# Arduino_Pro_Mini_Mother_Board_1_1.net
KiCad netlist of a schematic drawn in EAGLE
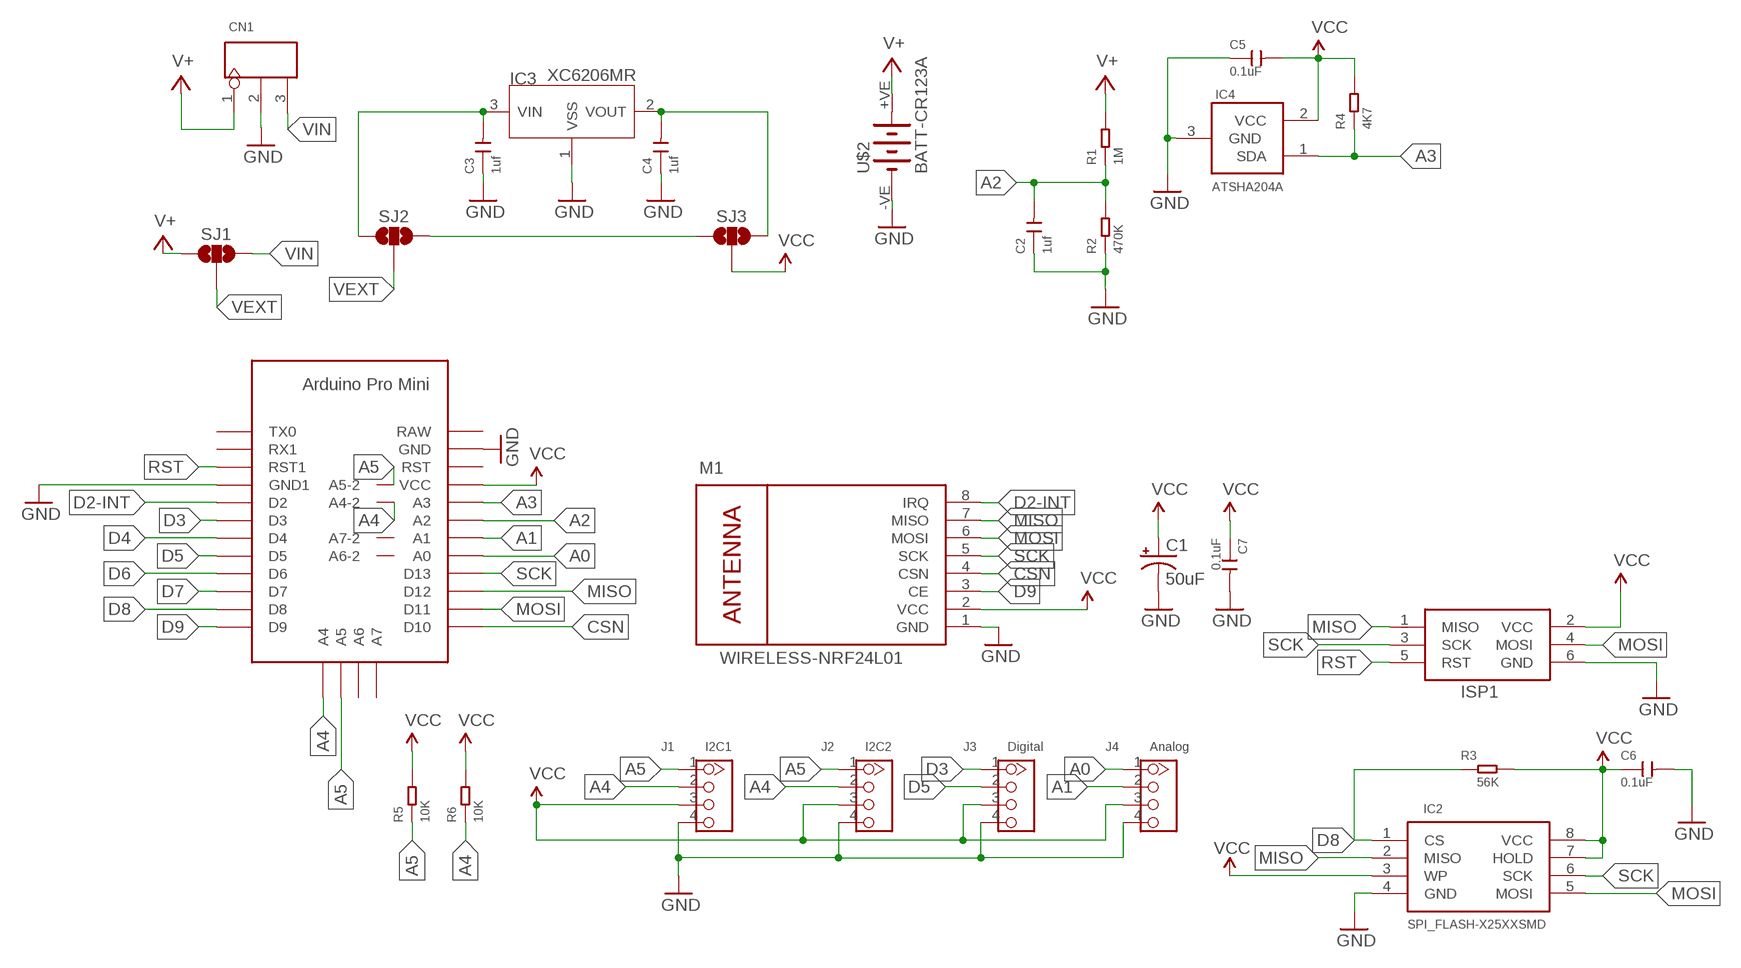
[diagram p0: schematic, sheet 1]

(export (version "E")
  (design (tool "Eeschema 10.0.6"))
  (components
    (comp (ref "ARDUINOPROMINI")
      (value "PRO-MINI-UNIVERSAL")
      (footprint "eagle-import:PRO-MINI-UINIVERSAL")
      (libsource (lib "eagle-import") (part "PRO-MINI-UNIVERSAL"))
    )
    (comp (ref "C1")
      (value "50uF")
      (footprint "eagle-import:EIA6032")
      (libsource (lib "eagle-import") (part "CAP_POL6032"))
    )
    (comp (ref "C2")
      (value "1uf")
      (footprint "eagle-import:C0603")
      (fields (field (name "MPN") "CC0603KRX7R8BB105"))
      (libsource (lib "eagle-import") (part "CERAMIC-1UF-25V-10%-X7R(0603)"))
    )
    (comp (ref "C3")
      (value "1uf")
      (footprint "eagle-import:C0603")
      (fields (field (name "MPN") "CC0603KRX7R8BB105"))
      (libsource (lib "eagle-import") (part "CERAMIC-1UF-25V-10%-X7R(0603)"))
    )
    (comp (ref "C4")
      (value "1uf")
      (footprint "eagle-import:C0603")
      (fields (field (name "MPN") "CC0603KRX7R8BB105"))
      (libsource (lib "eagle-import") (part "CERAMIC-1UF-25V-10%-X7R(0603)"))
    )
    (comp (ref "C5")
      (value "0.1uF")
      (footprint "eagle-import:C0603")
      (fields (field (name "MPN") "CC0603KRX7R8BB105"))
      (libsource (lib "eagle-import") (part "CERAMIC-1UF-25V-10%-X7R(0603)"))
    )
    (comp (ref "C6")
      (value "0.1uF")
      (footprint "eagle-import:C0603")
      (fields (field (name "MPN") "CC0603KRX7R8BB105"))
      (libsource (lib "eagle-import") (part "CERAMIC-1UF-25V-10%-X7R(0603)"))
    )
    (comp (ref "C7")
      (value "0.1uF")
      (footprint "eagle-import:C0603")
      (fields (field (name "MPN") "CC0603KRX7R8BB105"))
      (libsource (lib "eagle-import") (part "CERAMIC-1UF-25V-10%-X7R(0603)"))
    )
    (comp (ref "CN1")
      (value "DIP-BLACK-MALE-HEADER-VERT(3P-2.54)")
      (footprint "eagle-import:H3-2.54")
      (libsource (lib "eagle-import") (part "DIP-BLACK-MALE-HEADER-VERT(3P-2.54)"))
    )
    (comp (ref "IC2")
      (value "SPI_FLASH-X25XXSMD")
      (footprint "eagle-import:SO08")
      (libsource (lib "eagle-import") (part "SPI_FLASH-X25XXSMD"))
    )
    (comp (ref "IC3")
      (value "XC6206MR")
      (footprint "eagle-import:SOT23")
      (libsource (lib "eagle-import") (part "XC6206MR"))
    )
    (comp (ref "IC4")
      (value "ATSHA204A")
      (footprint "eagle-import:SOT23")
      (libsource (lib "eagle-import") (part "ATSHA204A"))
    )
    (comp (ref "ISP1")
      (value "AVRISP-6")
      (footprint "eagle-import:AVRISP")
      (libsource (lib "eagle-import") (part "AVRISP-6"))
    )
    (comp (ref "J1")
      (value "I2C1")
      (footprint "eagle-import:HW4-2.0")
      (libsource (lib "eagle-import") (part "GROVE-CONNECTOR-DIP(4P-2.0)"))
    )
    (comp (ref "J2")
      (value "I2C2")
      (footprint "eagle-import:HW4-2.0")
      (libsource (lib "eagle-import") (part "GROVE-CONNECTOR-DIP(4P-2.0)"))
    )
    (comp (ref "J3")
      (value "Digital")
      (footprint "eagle-import:HW4-2.0")
      (libsource (lib "eagle-import") (part "GROVE-CONNECTOR-DIP(4P-2.0)"))
    )
    (comp (ref "J4")
      (value "Analog")
      (footprint "eagle-import:HW4-2.0")
      (libsource (lib "eagle-import") (part "GROVE-CONNECTOR-DIP(4P-2.0)"))
    )
    (comp (ref "M1")
      (value "WIRELESS-NRF24L01")
      (footprint "eagle-import:WIRELESS-NRF24L01")
      (libsource (lib "eagle-import") (part "WIRELESS-NRF24L01"))
    )
    (comp (ref "R1")
      (value "1M")
      (footprint "eagle-import:R0603")
      (fields (field (name "MPN") "RC0603FR-071ML"))
      (libsource (lib "eagle-import") (part "SMD-RES-1M-1%-1/10W(0603)"))
    )
    (comp (ref "R2")
      (value "470K")
      (footprint "eagle-import:R0603")
      (fields (field (name "MPN") "RC0603FR-07470KL"))
      (libsource (lib "eagle-import") (part "SMD-RES-470K-1%-1/10W(0603)"))
    )
    (comp (ref "R3")
      (value "56K")
      (footprint "eagle-import:R0603")
      (fields (field (name "MPN") "RC0603FR-07470KL"))
      (libsource (lib "eagle-import") (part "SMD-RES-470K-1%-1/10W(0603)"))
    )
    (comp (ref "R4")
      (value "4K7")
      (footprint "eagle-import:R0603")
      (fields (field (name "MPN") "RC0603FR-07470KL"))
      (libsource (lib "eagle-import") (part "SMD-RES-470K-1%-1/10W(0603)"))
    )
    (comp (ref "R5")
      (value "10K")
      (footprint "eagle-import:R0603")
      (fields (field (name "MPN") "RC0603FR-071ML"))
      (libsource (lib "eagle-import") (part "SMD-RES-1M-1%-1/10W(0603)"))
    )
    (comp (ref "R6")
      (value "10K")
      (footprint "eagle-import:R0603")
      (fields (field (name "MPN") "RC0603FR-071ML"))
      (libsource (lib "eagle-import") (part "SMD-RES-1M-1%-1/10W(0603)"))
    )
    (comp (ref "SJ1")
      (value "SOLDERJUMPER_2WAYS")
      (footprint "eagle-import:SJ_3")
      (libsource (lib "eagle-import") (part "SOLDERJUMPER_2WAYS"))
    )
    (comp (ref "SJ2")
      (value "SOLDERJUMPER_2WAYS")
      (footprint "eagle-import:SJ_3")
      (libsource (lib "eagle-import") (part "SOLDERJUMPER_2WAYS"))
    )
    (comp (ref "SJ3")
      (value "SOLDERJUMPER_2WAYS")
      (footprint "eagle-import:SJ_3")
      (libsource (lib "eagle-import") (part "SOLDERJUMPER_2WAYS"))
    )
    (comp (ref "U$2")
      (value "BATT-CR123A")
      (footprint "eagle-import:KEYSTONE-2_3A")
      (libsource (lib "eagle-import") (part "BATT-CR123A"))
    )
  )
  (nets
    (net (code "1") (name "A0") (class "Default")
      (node (ref "ARDUINOPROMINI") (pin "A0") (pinfunction "A0_A0") (pintype "bidirectional"))
      (node (ref "J4") (pin "1") (pinfunction "1_1") (pintype "bidirectional"))
    )
    (net (code "2") (name "A1") (class "Default")
      (node (ref "ARDUINOPROMINI") (pin "A1") (pinfunction "A1_A1") (pintype "bidirectional"))
      (node (ref "J4") (pin "2") (pinfunction "2_2") (pintype "bidirectional"))
    )
    (net (code "3") (name "A2") (class "Default")
      (node (ref "ARDUINOPROMINI") (pin "A2") (pinfunction "A2_A2") (pintype "bidirectional"))
      (node (ref "C2") (pin "2") (pinfunction "2_2") (pintype "passive"))
      (node (ref "R1") (pin "1") (pinfunction "1_1") (pintype "passive"))
      (node (ref "R2") (pin "2") (pinfunction "2_2") (pintype "passive"))
    )
    (net (code "4") (name "A3") (class "Default")
      (node (ref "ARDUINOPROMINI") (pin "A3") (pinfunction "A3_A3") (pintype "bidirectional"))
      (node (ref "IC4") (pin "1") (pinfunction "SDA_1") (pintype "bidirectional"))
      (node (ref "R4") (pin "1") (pinfunction "1_1") (pintype "passive"))
    )
    (net (code "5") (name "A4") (class "Default")
      (node (ref "ARDUINOPROMINI") (pin "A4") (pinfunction "A4_A4") (pintype "bidirectional"))
      (node (ref "ARDUINOPROMINI") (pin "A4-2") (pinfunction "A4-2_A4-2") (pintype "bidirectional"))
      (node (ref "J1") (pin "2") (pinfunction "2_2") (pintype "bidirectional"))
      (node (ref "J2") (pin "2") (pinfunction "2_2") (pintype "bidirectional"))
      (node (ref "R6") (pin "1") (pinfunction "1_1") (pintype "passive"))
    )
    (net (code "6") (name "A5") (class "Default")
      (node (ref "ARDUINOPROMINI") (pin "A5") (pinfunction "A5_A5") (pintype "bidirectional"))
      (node (ref "ARDUINOPROMINI") (pin "A5-2") (pinfunction "A5-2_A5-2") (pintype "bidirectional"))
      (node (ref "J1") (pin "1") (pinfunction "1_1") (pintype "bidirectional"))
      (node (ref "J2") (pin "1") (pinfunction "1_1") (pintype "bidirectional"))
      (node (ref "R5") (pin "1") (pinfunction "1_1") (pintype "passive"))
    )
    (net (code "7") (name "CSN") (class "Default")
      (node (ref "ARDUINOPROMINI") (pin "D10") (pinfunction "D10_D10") (pintype "bidirectional"))
      (node (ref "M1") (pin "4") (pinfunction "CSN_4") (pintype "bidirectional"))
    )
    (net (code "8") (name "D2-INT") (class "Default")
      (node (ref "ARDUINOPROMINI") (pin "D2") (pinfunction "D2_D2") (pintype "bidirectional"))
      (node (ref "M1") (pin "8") (pinfunction "IRQ_8") (pintype "bidirectional"))
    )
    (net (code "9") (name "D3") (class "Default")
      (node (ref "ARDUINOPROMINI") (pin "D3") (pinfunction "D3_D3") (pintype "bidirectional"))
      (node (ref "J3") (pin "1") (pinfunction "1_1") (pintype "bidirectional"))
    )
    (net (code "10") (name "D4") (class "Default")
      (node (ref "ARDUINOPROMINI") (pin "D4") (pinfunction "D4_D4") (pintype "bidirectional"))
    )
    (net (code "11") (name "D5") (class "Default")
      (node (ref "ARDUINOPROMINI") (pin "D5") (pinfunction "D5_D5") (pintype "bidirectional"))
      (node (ref "J3") (pin "2") (pinfunction "2_2") (pintype "bidirectional"))
    )
    (net (code "12") (name "D6") (class "Default")
      (node (ref "ARDUINOPROMINI") (pin "D6") (pinfunction "D6_D6") (pintype "bidirectional"))
    )
    (net (code "13") (name "D7") (class "Default")
      (node (ref "ARDUINOPROMINI") (pin "D7") (pinfunction "D7_D7") (pintype "bidirectional"))
    )
    (net (code "14") (name "D8") (class "Default")
      (node (ref "ARDUINOPROMINI") (pin "D8") (pinfunction "D8_D8") (pintype "bidirectional"))
      (node (ref "IC2") (pin "1") (pinfunction "CS_1") (pintype "bidirectional"))
      (node (ref "R3") (pin "1") (pinfunction "1_1") (pintype "passive"))
    )
    (net (code "15") (name "D9") (class "Default")
      (node (ref "ARDUINOPROMINI") (pin "D9") (pinfunction "D9_D9") (pintype "bidirectional"))
      (node (ref "M1") (pin "3") (pinfunction "CE_3") (pintype "bidirectional"))
    )
    (net (code "16") (name "GND") (class "Default")
      (node (ref "ARDUINOPROMINI") (pin "GND0") (pinfunction "GND_GND0") (pintype "bidirectional"))
      (node (ref "ARDUINOPROMINI") (pin "GND1") (pinfunction "GND1_GND1") (pintype "bidirectional"))
      (node (ref "C1") (pin "P$2") (pinfunction "-_P$2") (pintype "passive"))
      (node (ref "C2") (pin "1") (pinfunction "1_1") (pintype "passive"))
      (node (ref "C3") (pin "1") (pinfunction "1_1") (pintype "passive"))
      (node (ref "C4") (pin "1") (pinfunction "1_1") (pintype "passive"))
      (node (ref "C5") (pin "1") (pinfunction "1_1") (pintype "passive"))
      (node (ref "C6") (pin "2") (pinfunction "2_2") (pintype "passive"))
      (node (ref "C7") (pin "2") (pinfunction "2_2") (pintype "passive"))
      (node (ref "CN1") (pin "2") (pinfunction "P$2_2") (pintype "bidirectional"))
      (node (ref "IC2") (pin "4") (pinfunction "GND_4") (pintype "bidirectional"))
      (node (ref "IC3") (pin "1") (pinfunction "VSS_1") (pintype "power_in"))
      (node (ref "IC4") (pin "3") (pinfunction "GND_3") (pintype "bidirectional"))
      (node (ref "ISP1") (pin "6") (pinfunction "GND_6") (pintype "power_in"))
      (node (ref "J1") (pin "4") (pinfunction "4_4") (pintype "bidirectional"))
      (node (ref "J2") (pin "4") (pinfunction "4_4") (pintype "bidirectional"))
      (node (ref "J3") (pin "4") (pinfunction "4_4") (pintype "bidirectional"))
      (node (ref "J4") (pin "4") (pinfunction "4_4") (pintype "bidirectional"))
      (node (ref "M1") (pin "1") (pinfunction "GND_1") (pintype "power_in"))
      (node (ref "R2") (pin "1") (pinfunction "1_1") (pintype "passive"))
      (node (ref "U$2") (pin "-VE") (pinfunction "-_-VE") (pintype "passive"))
    )
    (net (code "17") (name "MISO") (class "Default")
      (node (ref "ARDUINOPROMINI") (pin "D12") (pinfunction "D12_D12") (pintype "bidirectional"))
      (node (ref "IC2") (pin "2") (pinfunction "MISO_2") (pintype "bidirectional"))
      (node (ref "ISP1") (pin "1") (pinfunction "MISO_1") (pintype "input"))
      (node (ref "M1") (pin "7") (pinfunction "MISO_7") (pintype "bidirectional"))
    )
    (net (code "18") (name "MOSI") (class "Default")
      (node (ref "ARDUINOPROMINI") (pin "D11") (pinfunction "D11_D11") (pintype "bidirectional"))
      (node (ref "IC2") (pin "5") (pinfunction "MOSI_5") (pintype "bidirectional"))
      (node (ref "ISP1") (pin "4") (pinfunction "MOSI_4") (pintype "output"))
      (node (ref "M1") (pin "6") (pinfunction "MOSI_6") (pintype "bidirectional"))
    )
    (net (code "19") (name "Net-(IC3-VOUT)") (class "Default")
      (node (ref "C4") (pin "2") (pinfunction "2_2") (pintype "passive"))
      (node (ref "IC3") (pin "2") (pinfunction "VOUT_2") (pintype "output"))
      (node (ref "SJ3") (pin "3") (pinfunction "3_3") (pintype "passive"))
    )
    (net (code "20") (name "Net-(SJ2-Pad3)") (class "Default")
      (node (ref "SJ2") (pin "3") (pinfunction "3_3") (pintype "passive"))
      (node (ref "SJ3") (pin "1") (pinfunction "1_1") (pintype "passive"))
    )
    (net (code "21") (name "RST") (class "Default")
      (node (ref "ARDUINOPROMINI") (pin "RST1") (pinfunction "RST1_RST1") (pintype "bidirectional"))
      (node (ref "ISP1") (pin "5") (pinfunction "RST_5") (pintype "output"))
    )
    (net (code "22") (name "SCK") (class "Default")
      (node (ref "ARDUINOPROMINI") (pin "D13") (pinfunction "D13_D13") (pintype "bidirectional"))
      (node (ref "IC2") (pin "6") (pinfunction "SCK_6") (pintype "bidirectional"))
      (node (ref "ISP1") (pin "3") (pinfunction "SCK_3") (pintype "output"))
      (node (ref "M1") (pin "5") (pinfunction "SCK_5") (pintype "bidirectional"))
    )
    (net (code "23") (name "V+") (class "Default")
      (node (ref "CN1") (pin "1") (pinfunction "P$1_1") (pintype "bidirectional"))
      (node (ref "R1") (pin "2") (pinfunction "2_2") (pintype "passive"))
      (node (ref "SJ1") (pin "1") (pinfunction "1_1") (pintype "passive"))
      (node (ref "U$2") (pin "+VE") (pinfunction "+_+VE") (pintype "passive"))
    )
    (net (code "24") (name "VCC") (class "Default")
      (node (ref "ARDUINOPROMINI") (pin "VCC") (pinfunction "VCC_VCC") (pintype "bidirectional"))
      (node (ref "C1") (pin "P$1") (pinfunction "+_P$1") (pintype "passive"))
      (node (ref "C5") (pin "2") (pinfunction "2_2") (pintype "passive"))
      (node (ref "C6") (pin "1") (pinfunction "1_1") (pintype "passive"))
      (node (ref "C7") (pin "1") (pinfunction "1_1") (pintype "passive"))
      (node (ref "IC2") (pin "3") (pinfunction "WP_3") (pintype "bidirectional"))
      (node (ref "IC2") (pin "7") (pinfunction "HOLD_7") (pintype "bidirectional"))
      (node (ref "IC2") (pin "8") (pinfunction "VCC_8") (pintype "bidirectional"))
      (node (ref "IC4") (pin "2") (pinfunction "VCC_2") (pintype "bidirectional"))
      (node (ref "ISP1") (pin "2") (pinfunction "VCC_2") (pintype "power_in"))
      (node (ref "J1") (pin "3") (pinfunction "3_3") (pintype "bidirectional"))
      (node (ref "J2") (pin "3") (pinfunction "3_3") (pintype "bidirectional"))
      (node (ref "J3") (pin "3") (pinfunction "3_3") (pintype "bidirectional"))
      (node (ref "J4") (pin "3") (pinfunction "3_3") (pintype "bidirectional"))
      (node (ref "M1") (pin "2") (pinfunction "VCC_2") (pintype "power_in"))
      (node (ref "R3") (pin "2") (pinfunction "2_2") (pintype "passive"))
      (node (ref "R4") (pin "2") (pinfunction "2_2") (pintype "passive"))
      (node (ref "R5") (pin "2") (pinfunction "2_2") (pintype "passive"))
      (node (ref "R6") (pin "2") (pinfunction "2_2") (pintype "passive"))
      (node (ref "SJ3") (pin "2") (pinfunction "2_2") (pintype "passive"))
    )
    (net (code "25") (name "VEXT") (class "Default")
      (node (ref "SJ1") (pin "2") (pinfunction "2_2") (pintype "passive"))
      (node (ref "SJ2") (pin "2") (pinfunction "2_2") (pintype "passive"))
    )
    (net (code "26") (name "VIN") (class "Default")
      (node (ref "C3") (pin "2") (pinfunction "2_2") (pintype "passive"))
      (node (ref "CN1") (pin "3") (pinfunction "P$3_3") (pintype "bidirectional"))
      (node (ref "IC3") (pin "3") (pinfunction "VIN_3") (pintype "input"))
      (node (ref "SJ1") (pin "3") (pinfunction "3_3") (pintype "passive"))
      (node (ref "SJ2") (pin "1") (pinfunction "1_1") (pintype "passive"))
    )
    (net (code "27") (name "unconnected-(ARDUINOPROMINI-PadA6)") (class "Default")
      (node (ref "ARDUINOPROMINI") (pin "A6") (pinfunction "A6_A6") (pintype "bidirectional"))
    )
    (net (code "28") (name "unconnected-(ARDUINOPROMINI-PadA6-2)") (class "Default")
      (node (ref "ARDUINOPROMINI") (pin "A6-2") (pinfunction "A6-2_A6-2") (pintype "bidirectional"))
    )
    (net (code "29") (name "unconnected-(ARDUINOPROMINI-PadA7)") (class "Default")
      (node (ref "ARDUINOPROMINI") (pin "A7") (pinfunction "A7_A7") (pintype "bidirectional"))
    )
    (net (code "30") (name "unconnected-(ARDUINOPROMINI-PadA7-2)") (class "Default")
      (node (ref "ARDUINOPROMINI") (pin "A7-2") (pinfunction "A7-2_A7-2") (pintype "bidirectional"))
    )
    (net (code "31") (name "unconnected-(ARDUINOPROMINI-PadRAW)") (class "Default")
      (node (ref "ARDUINOPROMINI") (pin "RAW") (pinfunction "RAW_RAW") (pintype "bidirectional"))
    )
    (net (code "32") (name "unconnected-(ARDUINOPROMINI-PadRST)") (class "Default")
      (node (ref "ARDUINOPROMINI") (pin "RST") (pinfunction "RST_RST") (pintype "bidirectional"))
    )
    (net (code "33") (name "unconnected-(ARDUINOPROMINI-PadRX1)") (class "Default")
      (node (ref "ARDUINOPROMINI") (pin "RX1") (pinfunction "RX1_RX1") (pintype "bidirectional"))
    )
    (net (code "34") (name "unconnected-(ARDUINOPROMINI-PadTX0)") (class "Default")
      (node (ref "ARDUINOPROMINI") (pin "TX0") (pinfunction "TX0_TX0") (pintype "bidirectional"))
    )
  )
)
